# PR9022.net
KiCad netlist of a schematic drawn in EAGLE
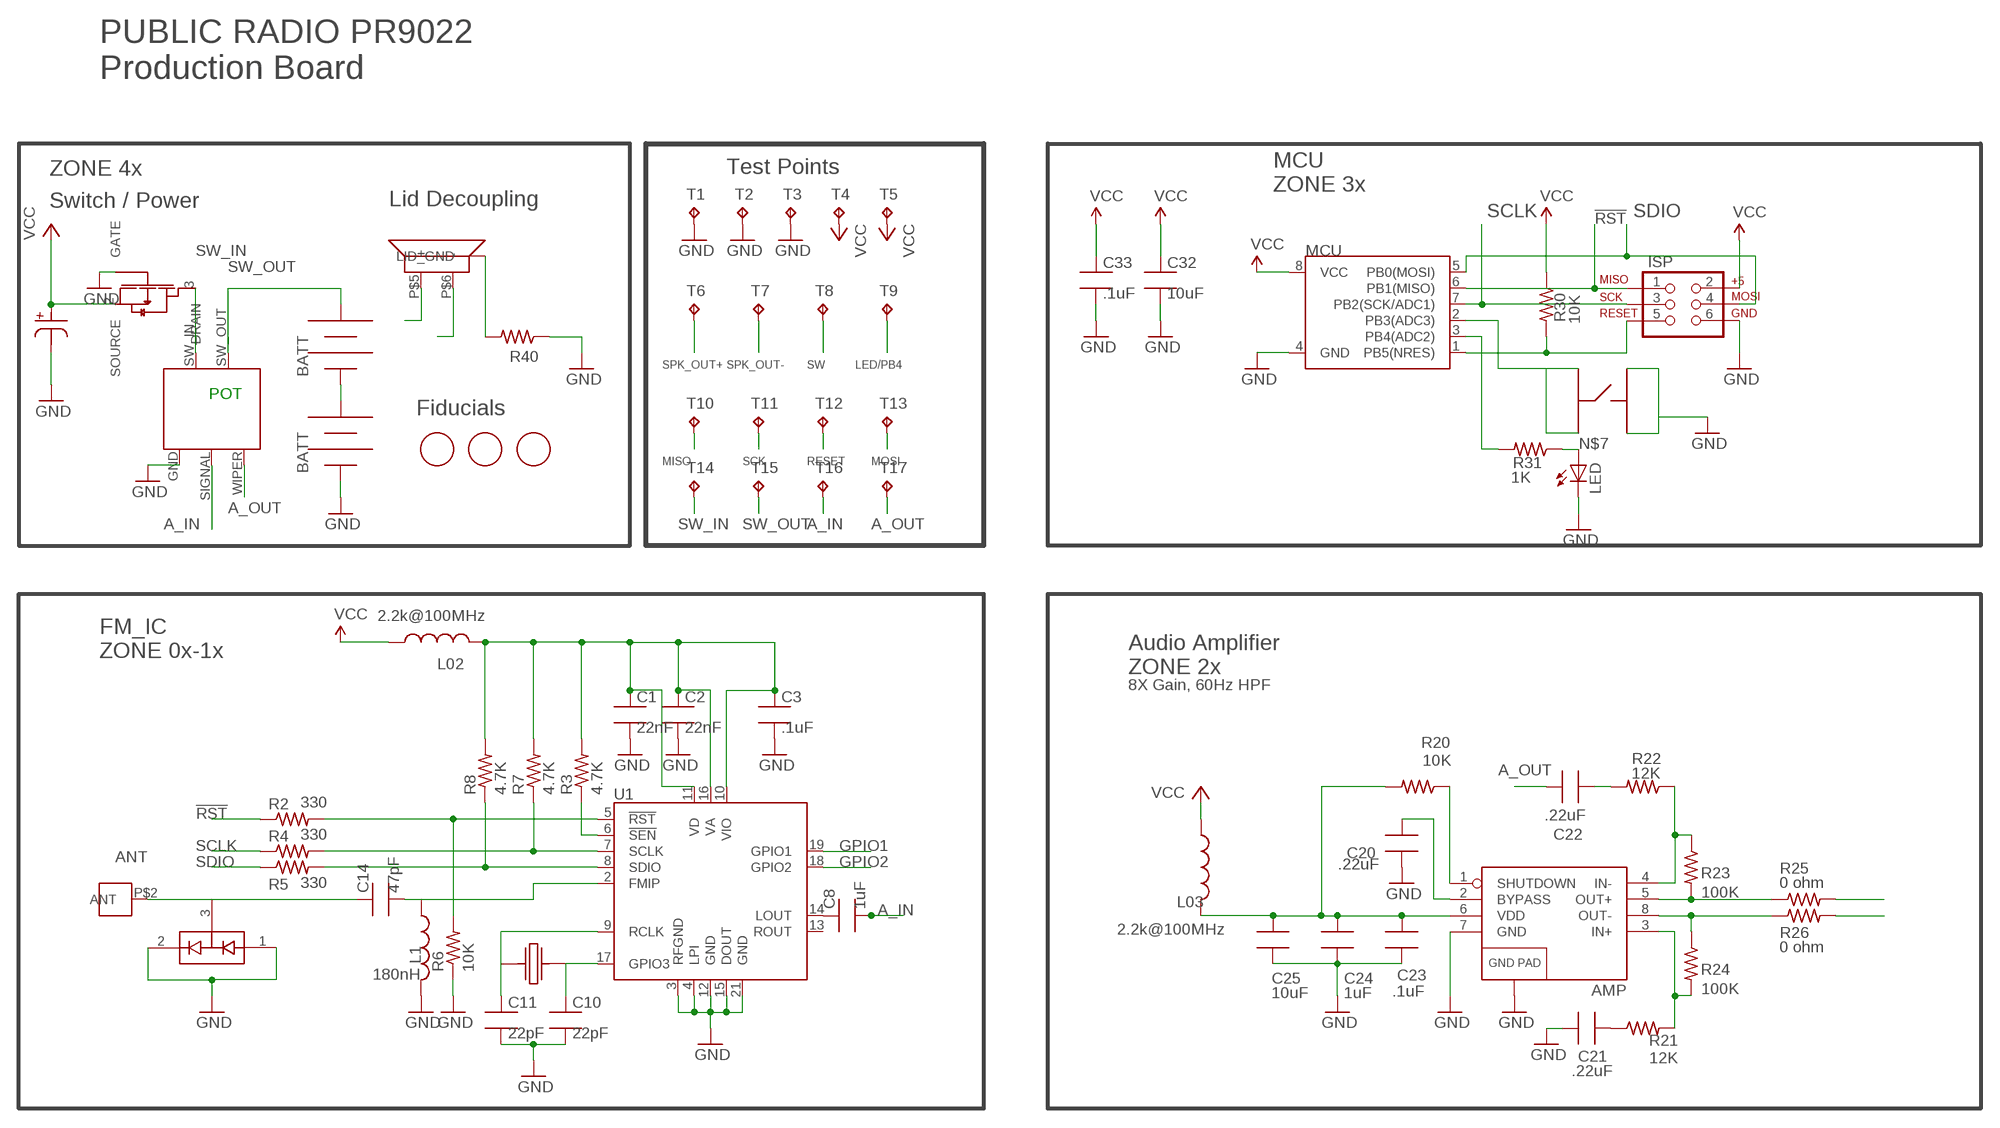
[diagram p0: schematic, sheet 1]

(export (version "E")
  (design (tool "Eeschema 10.0.6"))
  (components
    (comp (ref "AMP")
      (value "TPA6203A1")
      (footprint "eagle-import:8-MSOP")
      (libsource (lib "eagle-import") (part "TPA6203A1"))
    )
    (comp (ref "ANT_MOUNT")
      (value "DNP")
      (footprint "eagle-import:PEM_M3")
      (libsource (lib "eagle-import") (part "M3_PEMNUT"))
    )
    (comp (ref "C1")
      (value "22nF")
      (footprint "eagle-import:0603_CPL")
      (fields
        (field (name "MFG_PN") "CL10B223KB8NNNC")
        (field (name "TOL") "10%")
        (field (name "VOLTAGE") "16V")
      )
      (libsource (lib "eagle-import") (part "C_SMT_0603_CPL"))
    )
    (comp (ref "C2")
      (value "22nF")
      (footprint "eagle-import:0603_CPL")
      (fields
        (field (name "MFG_PN") "CL10B223KB8NNNC")
        (field (name "TOL") "10%")
        (field (name "VOLTAGE") "16V")
      )
      (libsource (lib "eagle-import") (part "C_SMT_0603_CPL"))
    )
    (comp (ref "C3")
      (value ".1uF")
      (footprint "eagle-import:0603_CPL")
      (fields
        (field (name "MFG_PN") "CL10B104KB8SFNC")
        (field (name "TOL") "10%")
        (field (name "VOLTAGE") "16V")
      )
      (libsource (lib "eagle-import") (part "C_SMT_0603_CPL"))
    )
    (comp (ref "C8")
      (value "1uF")
      (footprint "eagle-import:0603_CPL")
      (fields
        (field (name "MFG_PN") "CL10B105KP8NNNC")
        (field (name "TOL") "10%")
        (field (name "VOLTAGE") "10V")
      )
      (libsource (lib "eagle-import") (part "C_SMT_0603_CPL"))
    )
    (comp (ref "C10")
      (value "22pF")
      (footprint "eagle-import:0603_CPL")
      (fields
        (field (name "MFG_PN") "C1608C0G1H220J080AA")
        (field (name "TOL") "5%")
        (field (name "VOLTAGE") "50V")
      )
      (libsource (lib "eagle-import") (part "C_SMT_0603_CPL"))
    )
    (comp (ref "C11")
      (value "22pF")
      (footprint "eagle-import:0603_CPL")
      (fields
        (field (name "MFG_PN") "C1608C0G1H220J080AA")
        (field (name "TOL") "5%")
        (field (name "VOLTAGE") "50V")
      )
      (libsource (lib "eagle-import") (part "C_SMT_0603_CPL"))
    )
    (comp (ref "C14")
      (value "47pF")
      (footprint "eagle-import:0603_CPL")
      (fields
        (field (name "MFG_PN") "CL10C470JB8NCNC")
        (field (name "TOL") "5%")
        (field (name "VOLTAGE") "50V")
      )
      (libsource (lib "eagle-import") (part "C_SMT_0603_CPL"))
    )
    (comp (ref "C20")
      (value ".22uF")
      (footprint "eagle-import:0603_CPL")
      (fields
        (field (name "MFG_PN") "C1608X7R1C224K080AC")
        (field (name "TOL") "10%")
        (field (name "VOLTAGE") "16V")
      )
      (libsource (lib "eagle-import") (part "C_SMT_0603_CPL"))
    )
    (comp (ref "C21")
      (value ".22uF")
      (footprint "eagle-import:0603_CPL")
      (fields
        (field (name "MFG_PN") "C1608X7R1C224K080AC")
        (field (name "TOL") "10%")
        (field (name "VOLTAGE") "16V")
      )
      (libsource (lib "eagle-import") (part "C_SMT_0603_CPL"))
    )
    (comp (ref "C22")
      (value ".22uF")
      (footprint "eagle-import:0603_CPL")
      (fields
        (field (name "MFG_PN") "C1608X7R1C224K080AC")
        (field (name "TOL") "10%")
        (field (name "VOLTAGE") "16V")
      )
      (libsource (lib "eagle-import") (part "C_SMT_0603_CPL"))
    )
    (comp (ref "C23")
      (value ".1uF")
      (footprint "eagle-import:0603_CPL")
      (fields
        (field (name "MFG_PN") "CL10B104KB8SFNC")
        (field (name "TOL") "10%")
        (field (name "VOLTAGE") "16V")
      )
      (libsource (lib "eagle-import") (part "C_SMT_0603_CPL"))
    )
    (comp (ref "C24")
      (value "1uF")
      (footprint "eagle-import:0603_CPL")
      (fields
        (field (name "MFG_PN") "CL10B105KP8NNNC")
        (field (name "TOL") "10%")
        (field (name "VOLTAGE") "10V")
      )
      (libsource (lib "eagle-import") (part "C_SMT_0603_CPL"))
    )
    (comp (ref "C25")
      (value "10uF")
      (footprint "eagle-import:0603_CPL")
      (fields
        (field (name "MFG_PN") "CL10A106MQ8NNNC")
        (field (name "TOL") "20%")
        (field (name "VOLTAGE") "6.3V")
      )
      (libsource (lib "eagle-import") (part "C_SMT_0603_CPL"))
    )
    (comp (ref "C32")
      (value "10uF")
      (footprint "eagle-import:0603_CPL")
      (fields
        (field (name "MFG_PN") "CL10A106MQ8NNNC")
        (field (name "TOL") "20%")
        (field (name "VOLTAGE") "6.3V")
      )
      (libsource (lib "eagle-import") (part "C_SMT_0603_CPL"))
    )
    (comp (ref "C33")
      (value ".1uF")
      (footprint "eagle-import:0603_CPL")
      (fields
        (field (name "MFG_PN") "CL10B104KB8SFNC")
        (field (name "TOL") "10%")
        (field (name "VOLTAGE") "16V")
      )
      (libsource (lib "eagle-import") (part "C_SMT_0603_CPL"))
    )
    (comp (ref "C40")
      (value "220uF")
      (footprint "eagle-import:NICHICON_UD_63")
      (fields (field (name "TOL") "20%") (field (name "VOLTAGE") "16V"))
      (libsource (lib "eagle-import") (part "NICHICON_SERIESUD"))
    )
    (comp (ref "D1")
      (value "BAV99")
      (footprint "eagle-import:SOT23_CPL")
      (fields (field (name "MFG_PN") "BAV99,215"))
      (libsource (lib "eagle-import") (part "BAV99"))
    )
    (comp (ref "FET1")
      (value "AO3435")
      (footprint "eagle-import:SOT23_CPL")
      (fields (field (name "MFG_PN") "AO3435"))
      (libsource (lib "eagle-import") (part "AO3435"))
    )
    (comp (ref "ISP")
      (value "AVR_SPI_PRG_6NS")
      (footprint "eagle-import:2X3-NS")
      (libsource (lib "eagle-import") (part "AVR_SPI_PRG_6NS"))
    )
    (comp (ref "JP5")
      (value "BK-92_MPD_AA_BATT_CLIP")
      (footprint "eagle-import:BK92_AA_BATT")
      (fields (field (name "MFG_PN") "2 of BK92 - supplied by CL Labs"))
      (libsource (lib "eagle-import") (part "BK-92_MPD_AA_BATT_CLIP"))
    )
    (comp (ref "JP6")
      (value "BK-92_MPD_AA_BATT_CLIP")
      (footprint "eagle-import:BK92_AA_BATT")
      (fields (field (name "MFG_PN") "2 of BK92 - supplied by CL Labs"))
      (libsource (lib "eagle-import") (part "BK-92_MPD_AA_BATT_CLIP"))
    )
    (comp (ref "L1")
      (value "180nH")
      (footprint "eagle-import:0805_ADAFRUIT")
      (fields
        (field (name "CURRENT") "400mA")
        (field (name "DCR") "640m")
        (field (name "MFG_PN") "AISC-0805-R18J-T")
        (field (name "TOL") "5%")
      )
      (libsource (lib "eagle-import") (part "L_SMT_0805_ADAFRUIT"))
    )
    (comp (ref "L02")
      (value "2.2k@100MHz")
      (footprint "eagle-import:0603_CPL")
      (fields
        (field (name "CURRENT") "150mA")
        (field (name "DCR") "2.3")
        (field (name "MFG_PN") "HZ0603A222R-10")
      )
      (libsource (lib "eagle-import") (part "L_SMT_0603_CPL"))
    )
    (comp (ref "L03")
      (value "2.2k@100MHz")
      (footprint "eagle-import:0603_CPL")
      (fields
        (field (name "CURRENT") "150mA")
        (field (name "DCR") "2.3")
        (field (name "MFG_PN") "HZ0603A222R-10")
      )
      (libsource (lib "eagle-import") (part "L_SMT_0603_CPL"))
    )
    (comp (ref "LED")
      (value "LEDCHIPLED_0805")
      (footprint "eagle-import:CHIPLED_0805")
      (libsource (lib "eagle-import") (part "LEDCHIPLED_0805"))
    )
    (comp (ref "MARK1")
      (value "FIDUCIAL")
      (footprint "eagle-import:FIDUCIAL_1MM")
      (libsource (lib "eagle-import") (part "FIDUCIAL"))
    )
    (comp (ref "MARK2")
      (value "FIDUCIAL")
      (footprint "eagle-import:FIDUCIAL_1MM")
      (libsource (lib "eagle-import") (part "FIDUCIAL"))
    )
    (comp (ref "MARK3")
      (value "FIDUCIAL")
      (footprint "eagle-import:FIDUCIAL_1MM")
      (libsource (lib "eagle-import") (part "FIDUCIAL"))
    )
    (comp (ref "MCU")
      (value "ATTINY45TINY45-20-SMT")
      (footprint "eagle-import:8-SOIC")
      (libsource (lib "eagle-import") (part "ATTINY45TINY45-20-SMT"))
    )
    (comp (ref "R1")
      (value "RV170SF_TAIWANA_POT_SW")
      (footprint "eagle-import:RV170SF_SW_POT")
      (fields (field (name "MFG_PN") "RV170SF-43-20F-A10K - supplied by CL Labs"))
      (libsource (lib "eagle-import") (part "RV170SF_TAIWANA_POT_SW"))
    )
    (comp (ref "R2")
      (value "330")
      (footprint "eagle-import:0603_CPL")
      (fields (field (name "MFG_PN") "MCR03ERTJ331") (field (name "POWER") "1/10W") (field (name "TOL") "5%"))
      (libsource (lib "eagle-import") (part "R_SMT_R0603_CPL"))
    )
    (comp (ref "R3")
      (value "4.7K")
      (footprint "eagle-import:0603_CPL")
      (fields
        (field (name "MFG_PN") "ERJ-3EKF4701V")
        (field (name "POWER") "1/10W")
        (field (name "TOL") "1%")
      )
      (libsource (lib "eagle-import") (part "R_SMT_R0603_CPL"))
    )
    (comp (ref "R4")
      (value "330")
      (footprint "eagle-import:0603_CPL")
      (fields (field (name "MFG_PN") "MCR03ERTJ331") (field (name "POWER") "1/10W") (field (name "TOL") "5%"))
      (libsource (lib "eagle-import") (part "R_SMT_R0603_CPL"))
    )
    (comp (ref "R5")
      (value "330")
      (footprint "eagle-import:0603_CPL")
      (fields (field (name "MFG_PN") "MCR03ERTJ331") (field (name "POWER") "1/10W") (field (name "TOL") "5%"))
      (libsource (lib "eagle-import") (part "R_SMT_R0603_CPL"))
    )
    (comp (ref "R6")
      (value "10K")
      (footprint "eagle-import:0603_CPL")
      (fields
        (field (name "MFG_PN") "ERJ-3GEYJ103V")
        (field (name "POWER") "1/10W")
        (field (name "TOL") "5%")
      )
      (libsource (lib "eagle-import") (part "R_SMT_R0603_CPL"))
    )
    (comp (ref "R7")
      (value "4.7K")
      (footprint "eagle-import:0603_CPL")
      (fields
        (field (name "MFG_PN") "ERJ-3EKF4701V")
        (field (name "POWER") "1/10W")
        (field (name "TOL") "1%")
      )
      (libsource (lib "eagle-import") (part "R_SMT_R0603_CPL"))
    )
    (comp (ref "R8")
      (value "4.7K")
      (footprint "eagle-import:0603_CPL")
      (fields
        (field (name "MFG_PN") "ERJ-3EKF4701V")
        (field (name "POWER") "1/10W")
        (field (name "TOL") "1%")
      )
      (libsource (lib "eagle-import") (part "R_SMT_R0603_CPL"))
    )
    (comp (ref "R20")
      (value "10K")
      (footprint "eagle-import:0603_CPL")
      (fields
        (field (name "MFG_PN") "ERJ-3GEYJ103V")
        (field (name "POWER") "1/10W")
        (field (name "TOL") "5%")
      )
      (libsource (lib "eagle-import") (part "R_SMT_R0603_CPL"))
    )
    (comp (ref "R21")
      (value "12K")
      (footprint "eagle-import:0603_CPL")
      (fields
        (field (name "MFG_PN") "RC0603FR-0712KL")
        (field (name "POWER") "1/10W")
        (field (name "TOL") "1%")
      )
      (libsource (lib "eagle-import") (part "R_SMT_R0603_CPL"))
    )
    (comp (ref "R22")
      (value "12K")
      (footprint "eagle-import:0603_CPL")
      (fields
        (field (name "MFG_PN") "RC0603FR-0712KL")
        (field (name "POWER") "1/10W")
        (field (name "TOL") "1%")
      )
      (libsource (lib "eagle-import") (part "R_SMT_R0603_CPL"))
    )
    (comp (ref "R23")
      (value "100K")
      (footprint "eagle-import:0603_CPL")
      (fields
        (field (name "MFG_PN") "ERJ-3EKF1003V")
        (field (name "POWER") "1/10W")
        (field (name "TOL") "1%")
      )
      (libsource (lib "eagle-import") (part "R_SMT_R0603_CPL"))
    )
    (comp (ref "R24")
      (value "100K")
      (footprint "eagle-import:0603_CPL")
      (fields
        (field (name "MFG_PN") "ERJ-3EKF1003V")
        (field (name "POWER") "1/10W")
        (field (name "TOL") "1%")
      )
      (libsource (lib "eagle-import") (part "R_SMT_R0603_CPL"))
    )
    (comp (ref "R25")
      (value "0 ohm")
      (footprint "eagle-import:0805_ADAFRUIT")
      (fields (field (name "MFG_PN") "ERJ-6GEY0R00V "))
      (libsource (lib "eagle-import") (part "R_SMT_0805_ADAFRUIT"))
    )
    (comp (ref "R26")
      (value "0 ohm")
      (footprint "eagle-import:0805_ADAFRUIT")
      (fields (field (name "MFG_PN") "ERJ-6GEY0R00V "))
      (libsource (lib "eagle-import") (part "R_SMT_0805_ADAFRUIT"))
    )
    (comp (ref "R30")
      (value "10K")
      (footprint "eagle-import:0603_CPL")
      (fields
        (field (name "MFG_PN") "ERJ-3GEYJ103V")
        (field (name "POWER") "1/10W")
        (field (name "TOL") "5%")
      )
      (libsource (lib "eagle-import") (part "R_SMT_R0603_CPL"))
    )
    (comp (ref "R31")
      (value "1K")
      (footprint "eagle-import:0603_CPL")
      (fields
        (field (name "MFG_PN") "ERJ-3EKF1001V")
        (field (name "POWER") "1/10W")
        (field (name "TOL") "1%")
      )
      (libsource (lib "eagle-import") (part "R_SMT_R0603_CPL"))
    )
    (comp (ref "R40")
      (value "DNP")
      (footprint "eagle-import:0603_CPL")
      (fields (field (name "MFG_PN") "ERJ-3GEY0R00V"))
      (libsource (lib "eagle-import") (part "R_SMT_R0603_CPL"))
    )
    (comp (ref "SPKR_PLACE")
      (value "DNP")
      (footprint "eagle-import:PR2024_SPKR_PLACE")
      (libsource (lib "eagle-import") (part "PR9024_SPKR"))
    )
    (comp (ref "SW1")
      (value "C&K_PTS645")
      (footprint "eagle-import:C&K_PTS645_SMT")
      (libsource (lib "eagle-import") (part "C&K_PTS645"))
    )
    (comp (ref "T1")
      (value "TPTP20R")
      (footprint "eagle-import:TP20R")
      (libsource (lib "eagle-import") (part "TPTP20R"))
    )
    (comp (ref "T2")
      (value "TPTP20R")
      (footprint "eagle-import:TP20R")
      (libsource (lib "eagle-import") (part "TPTP20R"))
    )
    (comp (ref "T3")
      (value "TPTP20R")
      (footprint "eagle-import:TP20R")
      (libsource (lib "eagle-import") (part "TPTP20R"))
    )
    (comp (ref "T4")
      (value "TPTP20R")
      (footprint "eagle-import:TP20R")
      (libsource (lib "eagle-import") (part "TPTP20R"))
    )
    (comp (ref "T5")
      (value "TPTP20R")
      (footprint "eagle-import:TP20R")
      (libsource (lib "eagle-import") (part "TPTP20R"))
    )
    (comp (ref "T6")
      (value "TPTP20R")
      (footprint "eagle-import:TP20R")
      (libsource (lib "eagle-import") (part "TPTP20R"))
    )
    (comp (ref "T7")
      (value "TPTP20R")
      (footprint "eagle-import:TP20R")
      (libsource (lib "eagle-import") (part "TPTP20R"))
    )
    (comp (ref "T8")
      (value "TPTP20R")
      (footprint "eagle-import:TP20R")
      (libsource (lib "eagle-import") (part "TPTP20R"))
    )
    (comp (ref "T9")
      (value "TPTP20R")
      (footprint "eagle-import:TP20R")
      (libsource (lib "eagle-import") (part "TPTP20R"))
    )
    (comp (ref "T10")
      (value "TPTP20R")
      (footprint "eagle-import:TP20R")
      (libsource (lib "eagle-import") (part "TPTP20R"))
    )
    (comp (ref "T11")
      (value "TPTP20R")
      (footprint "eagle-import:TP20R")
      (libsource (lib "eagle-import") (part "TPTP20R"))
    )
    (comp (ref "T12")
      (value "TPTP20R")
      (footprint "eagle-import:TP20R")
      (libsource (lib "eagle-import") (part "TPTP20R"))
    )
    (comp (ref "T13")
      (value "TPTP20R")
      (footprint "eagle-import:TP20R")
      (libsource (lib "eagle-import") (part "TPTP20R"))
    )
    (comp (ref "T14")
      (value "TPTP20R")
      (footprint "eagle-import:TP20R")
      (libsource (lib "eagle-import") (part "TPTP20R"))
    )
    (comp (ref "T15")
      (value "TPTP20R")
      (footprint "eagle-import:TP20R")
      (libsource (lib "eagle-import") (part "TPTP20R"))
    )
    (comp (ref "T16")
      (value "TPTP20R")
      (footprint "eagle-import:TP20R")
      (libsource (lib "eagle-import") (part "TPTP20R"))
    )
    (comp (ref "T17")
      (value "TPTP20R")
      (footprint "eagle-import:TP20R")
      (libsource (lib "eagle-import") (part "TPTP20R"))
    )
    (comp (ref "U1")
      (value "SI4702-C19-GMR")
      (footprint "eagle-import:SI470X_20_QFN")
      (fields (field (name "MFG_PN") "Si4702 C19 GM - supplied by CL Labs"))
      (libsource (lib "eagle-import") (part "SI4702-C19-GMR"))
    )
    (comp (ref "X1")
      (value "ABS25XTAL")
      (footprint "eagle-import:4-SOJ")
      (libsource (lib "eagle-import") (part "ABS25XTAL"))
    )
  )
  (nets
    (net (code "1") (name "/ANT") (class "Default")
      (node (ref "ANT_MOUNT") (pin "P$2") (pinfunction "ANT_P$2") (pintype "bidirectional"))
      (node (ref "C14") (pin "1") (pinfunction "1_1") (pintype "passive"))
      (node (ref "D1") (pin "3") (pinfunction "COM_3") (pintype "bidirectional"))
    )
    (net (code "2") (name "/A_IN") (class "Default")
      (node (ref "C8") (pin "2") (pinfunction "2_2") (pintype "passive"))
      (node (ref "R1") (pin "SIGNAL") (pinfunction "SIGNAL_SIGNAL") (pintype "bidirectional"))
      (node (ref "T16") (pin "TP") (pinfunction "TP_TP") (pintype "input"))
    )
    (net (code "3") (name "/A_OUT") (class "Default")
      (node (ref "C22") (pin "2") (pinfunction "2_2") (pintype "passive"))
      (node (ref "R1") (pin "WIPER") (pinfunction "WIPER_WIPER") (pintype "bidirectional"))
      (node (ref "T17") (pin "TP") (pinfunction "TP_TP") (pintype "input"))
    )
    (net (code "4") (name "/GPIO1") (class "Default")
      (node (ref "U1") (pin "19") (pinfunction "GPIO1_19") (pintype "bidirectional"))
    )
    (net (code "5") (name "/GPIO2") (class "Default")
      (node (ref "U1") (pin "18") (pinfunction "GPIO2_18") (pintype "bidirectional"))
    )
    (net (code "6") (name "/LED{slash}PB4") (class "Default")
      (node (ref "MCU") (pin "3") (pinfunction "PB4(ADC2)_3") (pintype "bidirectional"))
      (node (ref "R31") (pin "2") (pinfunction "2_2") (pintype "passive"))
      (node (ref "T9") (pin "TP") (pinfunction "TP_TP") (pintype "input"))
    )
    (net (code "7") (name "/N$7") (class "Default")
      (node (ref "LED") (pin "A") (pinfunction "A_A") (pintype "passive"))
      (node (ref "R31") (pin "1") (pinfunction "1_1") (pintype "passive"))
    )
    (net (code "8") (name "/RESET") (class "Default")
      (node (ref "ISP") (pin "5") (pinfunction "5_5") (pintype "passive"))
      (node (ref "MCU") (pin "1") (pinfunction "PB5(NRES)_1") (pintype "bidirectional"))
      (node (ref "R30") (pin "2") (pinfunction "2_2") (pintype "passive"))
      (node (ref "T12") (pin "TP") (pinfunction "TP_TP") (pintype "input"))
    )
    (net (code "9") (name "/SCLK") (class "Default")
      (node (ref "ISP") (pin "3") (pinfunction "3_3") (pintype "passive"))
      (node (ref "MCU") (pin "7") (pinfunction "PB2(SCK/ADC1)_7") (pintype "bidirectional"))
      (node (ref "R4") (pin "1") (pinfunction "1_1") (pintype "passive"))
      (node (ref "T11") (pin "TP") (pinfunction "TP_TP") (pintype "input"))
    )
    (net (code "10") (name "/SDIO") (class "Default")
      (node (ref "ISP") (pin "4") (pinfunction "4_4") (pintype "passive"))
      (node (ref "MCU") (pin "5") (pinfunction "PB0(MOSI)_5") (pintype "bidirectional"))
      (node (ref "R5") (pin "1") (pinfunction "1_1") (pintype "passive"))
      (node (ref "T13") (pin "TP") (pinfunction "TP_TP") (pintype "input"))
    )
    (net (code "11") (name "/SPK_OUT+") (class "Default")
      (node (ref "R25") (pin "2") (pinfunction "2_2") (pintype "passive"))
      (node (ref "SPKR_PLACE") (pin "P$6") (pinfunction "-_P$6") (pintype "bidirectional"))
      (node (ref "T6") (pin "TP") (pinfunction "TP_TP") (pintype "input"))
    )
    (net (code "12") (name "/SPK_OUT-") (class "Default")
      (node (ref "R26") (pin "2") (pinfunction "2_2") (pintype "passive"))
      (node (ref "SPKR_PLACE") (pin "P$5") (pinfunction "+_P$5") (pintype "bidirectional"))
      (node (ref "T7") (pin "TP") (pinfunction "TP_TP") (pintype "input"))
    )
    (net (code "13") (name "/SW") (class "Default")
      (node (ref "MCU") (pin "2") (pinfunction "PB3(ADC3)_2") (pintype "bidirectional"))
      (node (ref "SW1") (pin "P$3") (pinfunction "P$3_P$3") (pintype "bidirectional"))
      (node (ref "SW1") (pin "P$4") (pinfunction "P$4_P$4") (pintype "bidirectional"))
      (node (ref "T8") (pin "TP") (pinfunction "TP_TP") (pintype "input"))
    )
    (net (code "14") (name "/SW_IN") (class "Default")
      (node (ref "FET1") (pin "3") (pinfunction "DRAIN_3") (pintype "bidirectional"))
      (node (ref "R1") (pin "SW_IN") (pinfunction "SW_IN_SW_IN") (pintype "bidirectional"))
      (node (ref "T14") (pin "TP") (pinfunction "TP_TP") (pintype "input"))
    )
    (net (code "15") (name "/SW_OUT") (class "Default")
      (node (ref "JP5") (pin "POS") (pinfunction "POS_POS") (pintype "bidirectional"))
      (node (ref "JP5") (pin "POS@2") (pinfunction "POS_POS@2") (pintype "bidirectional"))
      (node (ref "R1") (pin "SW_OUT") (pinfunction "SW_OUT_SW_OUT") (pintype "bidirectional"))
      (node (ref "T15") (pin "TP") (pinfunction "TP_TP") (pintype "input"))
    )
    (net (code "16") (name "/~{RST}") (class "Default")
      (node (ref "ISP") (pin "1") (pinfunction "1_1") (pintype "passive"))
      (node (ref "MCU") (pin "6") (pinfunction "PB1(MISO)_6") (pintype "bidirectional"))
      (node (ref "R2") (pin "1") (pinfunction "1_1") (pintype "passive"))
      (node (ref "T10") (pin "TP") (pinfunction "TP_TP") (pintype "input"))
    )
    (net (code "17") (name "GND") (class "Default")
      (node (ref "AMP") (pin "7") (pinfunction "GND_7") (pintype "power_in"))
      (node (ref "AMP") (pin "9") (pinfunction "GND_9") (pintype "power_in"))
      (node (ref "C1") (pin "2") (pinfunction "2_2") (pintype "passive"))
      (node (ref "C10") (pin "2") (pinfunction "2_2") (pintype "passive"))
      (node (ref "C11") (pin "2") (pinfunction "2_2") (pintype "passive"))
      (node (ref "C2") (pin "2") (pinfunction "2_2") (pintype "passive"))
      (node (ref "C20") (pin "1") (pinfunction "1_1") (pintype "passive"))
      (node (ref "C21") (pin "1") (pinfunction "1_1") (pintype "passive"))
      (node (ref "C23") (pin "2") (pinfunction "2_2") (pintype "passive"))
      (node (ref "C24") (pin "2") (pinfunction "2_2") (pintype "passive"))
      (node (ref "C25") (pin "2") (pinfunction "2_2") (pintype "passive"))
      (node (ref "C3") (pin "2") (pinfunction "2_2") (pintype "passive"))
      (node (ref "C32") (pin "2") (pinfunction "2_2") (pintype "passive"))
      (node (ref "C33") (pin "2") (pinfunction "2_2") (pintype "passive"))
      (node (ref "C40") (pin "P$2") (pinfunction "P$2_P$2") (pintype "bidirectional"))
      (node (ref "D1") (pin "1") (pinfunction "A1_1") (pintype "bidirectional"))
      (node (ref "D1") (pin "2") (pinfunction "C2_2") (pintype "bidirectional"))
      (node (ref "FET1") (pin "1") (pinfunction "GATE_1") (pintype "bidirectional"))
      (node (ref "ISP") (pin "6") (pinfunction "6_6") (pintype "passive"))
      (node (ref "JP6") (pin "NEG") (pinfunction "NEG_NEG") (pintype "bidirectional"))
      (node (ref "JP6") (pin "NEG@2") (pinfunction "NEG_NEG@2") (pintype "bidirectional"))
      (node (ref "L1") (pin "2") (pinfunction "2_2") (pintype "passive"))
      (node (ref "LED") (pin "C") (pinfunction "C_C") (pintype "passive"))
      (node (ref "MCU") (pin "4") (pinfunction "GND_4") (pintype "bidirectional"))
      (node (ref "R1") (pin "GND") (pinfunction "GND_GND") (pintype "bidirectional"))
      (node (ref "R40") (pin "1") (pinfunction "1_1") (pintype "passive"))
      (node (ref "R6") (pin "1") (pinfunction "1_1") (pintype "passive"))
      (node (ref "SW1") (pin "P$1") (pinfunction "P$1_P$1") (pintype "bidirectional"))
      (node (ref "SW1") (pin "P$2") (pinfunction "P$2_P$2") (pintype "bidirectional"))
      (node (ref "T1") (pin "TP") (pinfunction "TP_TP") (pintype "input"))
      (node (ref "T2") (pin "TP") (pinfunction "TP_TP") (pintype "input"))
      (node (ref "T3") (pin "TP") (pinfunction "TP_TP") (pintype "input"))
      (node (ref "U1") (pin "12") (pinfunction "GND_12") (pintype "bidirectional"))
      (node (ref "U1") (pin "15") (pinfunction "DOUT_15") (pintype "bidirectional"))
      (node (ref "U1") (pin "21") (pinfunction "GND_21") (pintype "bidirectional"))
      (node (ref "U1") (pin "3") (pinfunction "RFGND_3") (pintype "bidirectional"))
      (node (ref "U1") (pin "4") (pinfunction "LPI_4") (pintype "bidirectional"))
    )
    (net (code "18") (name "Net-(AMP-BYPASS)") (class "Default")
      (node (ref "AMP") (pin "2") (pinfunction "BYPASS_2") (pintype "bidirectional"))
      (node (ref "C20") (pin "2") (pinfunction "2_2") (pintype "passive"))
    )
    (net (code "19") (name "Net-(AMP-IN+)") (class "Default")
      (node (ref "AMP") (pin "3") (pinfunction "IN+_3") (pintype "bidirectional"))
      (node (ref "R21") (pin "2") (pinfunction "2_2") (pintype "passive"))
      (node (ref "R24") (pin "2") (pinfunction "2_2") (pintype "passive"))
    )
    (net (code "20") (name "Net-(AMP-IN-)") (class "Default")
      (node (ref "AMP") (pin "4") (pinfunction "IN-_4") (pintype "bidirectional"))
      (node (ref "R22") (pin "1") (pinfunction "1_1") (pintype "passive"))
      (node (ref "R23") (pin "1") (pinfunction "1_1") (pintype "passive"))
    )
    (net (code "21") (name "Net-(AMP-OUT+)") (class "Default")
      (node (ref "AMP") (pin "5") (pinfunction "OUT+_5") (pintype "bidirectional"))
      (node (ref "R23") (pin "2") (pinfunction "2_2") (pintype "passive"))
      (node (ref "R25") (pin "1") (pinfunction "1_1") (pintype "passive"))
    )
    (net (code "22") (name "Net-(AMP-OUT-)") (class "Default")
      (node (ref "AMP") (pin "8") (pinfunction "OUT-_8") (pintype "bidirectional"))
      (node (ref "R24") (pin "1") (pinfunction "1_1") (pintype "passive"))
      (node (ref "R26") (pin "1") (pinfunction "1_1") (pintype "passive"))
    )
    (net (code "23") (name "Net-(AMP-SHUTDOWN)") (class "Default")
      (node (ref "AMP") (pin "1") (pinfunction "SHUTDOWN_1") (pintype "input"))
      (node (ref "R20") (pin "1") (pinfunction "1_1") (pintype "passive"))
    )
    (net (code "24") (name "Net-(AMP-VDD)") (class "Default")
      (node (ref "AMP") (pin "6") (pinfunction "VDD_6") (pintype "power_in"))
      (node (ref "C23") (pin "1") (pinfunction "1_1") (pintype "passive"))
      (node (ref "C24") (pin "1") (pinfunction "1_1") (pintype "passive"))
      (node (ref "C25") (pin "1") (pinfunction "1_1") (pintype "passive"))
      (node (ref "L03") (pin "2") (pinfunction "2_2") (pintype "passive"))
      (node (ref "R20") (pin "2") (pinfunction "2_2") (pintype "passive"))
    )
    (net (code "25") (name "Net-(C21-Pad2)") (class "Default")
      (node (ref "C21") (pin "2") (pinfunction "2_2") (pintype "passive"))
      (node (ref "R21") (pin "1") (pinfunction "1_1") (pintype "passive"))
    )
    (net (code "26") (name "Net-(C22-Pad1)") (class "Default")
      (node (ref "C22") (pin "1") (pinfunction "1_1") (pintype "passive"))
      (node (ref "R22") (pin "2") (pinfunction "2_2") (pintype "passive"))
    )
    (net (code "27") (name "Net-(JP5-NEG-PadNEG@2)") (class "Default")
      (node (ref "JP5") (pin "NEG") (pinfunction "NEG_NEG") (pintype "bidirectional"))
      (node (ref "JP5") (pin "NEG@2") (pinfunction "NEG_NEG@2") (pintype "bidirectional"))
      (node (ref "JP6") (pin "POS") (pinfunction "POS_POS") (pintype "bidirectional"))
      (node (ref "JP6") (pin "POS@2") (pinfunction "POS_POS@2") (pintype "bidirectional"))
    )
    (net (code "28") (name "Net-(SPKR_PLACE-LID_GND)") (class "Default")
      (node (ref "R40") (pin "2") (pinfunction "2_2") (pintype "passive"))
      (node (ref "SPKR_PLACE") (pin "P$4") (pinfunction "LID_GND_P$4") (pintype "bidirectional"))
    )
    (net (code "29") (name "Net-(U1-FMIP)") (class "Default")
      (node (ref "C14") (pin "2") (pinfunction "2_2") (pintype "passive"))
      (node (ref "L1") (pin "1") (pinfunction "1_1") (pintype "passive"))
      (node (ref "U1") (pin "2") (pinfunction "FMIP_2") (pintype "bidirectional"))
    )
    (net (code "30") (name "Net-(U1-GPIO3)") (class "Default")
      (node (ref "C10") (pin "1") (pinfunction "1_1") (pintype "passive"))
      (node (ref "U1") (pin "17") (pinfunction "GPIO3_17") (pintype "bidirectional"))
      (node (ref "X1") (pin "P$4") (pinfunction "P$4_P$4") (pintype "bidirectional"))
    )
    (net (code "31") (name "Net-(U1-LOUT)") (class "Default")
      (node (ref "C8") (pin "1") (pinfunction "1_1") (pintype "passive"))
      (node (ref "U1") (pin "14") (pinfunction "LOUT_14") (pintype "bidirectional"))
    )
    (net (code "32") (name "Net-(U1-RCLK)") (class "Default")
      (node (ref "C11") (pin "1") (pinfunction "1_1") (pintype "passive"))
      (node (ref "U1") (pin "9") (pinfunction "RCLK_9") (pintype "bidirectional"))
      (node (ref "X1") (pin "P$1") (pinfunction "P$1_P$1") (pintype "bidirectional"))
    )
    (net (code "33") (name "Net-(U1-SCLK)") (class "Default")
      (node (ref "R4") (pin "2") (pinfunction "2_2") (pintype "passive"))
      (node (ref "R7") (pin "1") (pinfunction "1_1") (pintype "passive"))
      (node (ref "U1") (pin "7") (pinfunction "SCLK_7") (pintype "bidirectional"))
    )
    (net (code "34") (name "Net-(U1-SDIO)") (class "Default")
      (node (ref "R5") (pin "2") (pinfunction "2_2") (pintype "passive"))
      (node (ref "R8") (pin "1") (pinfunction "1_1") (pintype "passive"))
      (node (ref "U1") (pin "8") (pinfunction "SDIO_8") (pintype "bidirectional"))
    )
    (net (code "35") (name "Net-(U1-VA)") (class "Default")
      (node (ref "C1") (pin "1") (pinfunction "1_1") (pintype "passive"))
      (node (ref "C2") (pin "1") (pinfunction "1_1") (pintype "passive"))
      (node (ref "C3") (pin "1") (pinfunction "1_1") (pintype "passive"))
      (node (ref "L02") (pin "2") (pinfunction "2_2") (pintype "passive"))
      (node (ref "R3") (pin "2") (pinfunction "2_2") (pintype "passive"))
      (node (ref "R7") (pin "2") (pinfunction "2_2") (pintype "passive"))
      (node (ref "R8") (pin "2") (pinfunction "2_2") (pintype "passive"))
      (node (ref "U1") (pin "10") (pinfunction "VIO_10") (pintype "bidirectional"))
      (node (ref "U1") (pin "11") (pinfunction "VD_11") (pintype "bidirectional"))
      (node (ref "U1") (pin "16") (pinfunction "VA_16") (pintype "bidirectional"))
    )
    (net (code "36") (name "Net-(U1-~{RST})") (class "Default")
      (node (ref "R2") (pin "2") (pinfunction "2_2") (pintype "passive"))
      (node (ref "R6") (pin "2") (pinfunction "2_2") (pintype "passive"))
      (node (ref "U1") (pin "5") (pinfunction "~{RST}_5") (pintype "bidirectional"))
    )
    (net (code "37") (name "Net-(U1-~{SEN})") (class "Default")
      (node (ref "R3") (pin "1") (pinfunction "1_1") (pintype "passive"))
      (node (ref "U1") (pin "6") (pinfunction "~{SEN}_6") (pintype "bidirectional"))
    )
    (net (code "38") (name "VCC") (class "Default")
      (node (ref "C32") (pin "1") (pinfunction "1_1") (pintype "passive"))
      (node (ref "C33") (pin "1") (pinfunction "1_1") (pintype "passive"))
      (node (ref "C40") (pin "P$1") (pinfunction "P$1_P$1") (pintype "bidirectional"))
      (node (ref "FET1") (pin "2") (pinfunction "SOURCE_2") (pintype "bidirectional"))
      (node (ref "ISP") (pin "2") (pinfunction "2_2") (pintype "passive"))
      (node (ref "L02") (pin "1") (pinfunction "1_1") (pintype "passive"))
      (node (ref "L03") (pin "1") (pinfunction "1_1") (pintype "passive"))
      (node (ref "MCU") (pin "8") (pinfunction "VCC_8") (pintype "bidirectional"))
      (node (ref "R30") (pin "1") (pinfunction "1_1") (pintype "passive"))
      (node (ref "T4") (pin "TP") (pinfunction "TP_TP") (pintype "input"))
      (node (ref "T5") (pin "TP") (pinfunction "TP_TP") (pintype "input"))
    )
    (net (code "39") (name "unconnected-(U1-ROUT-Pad13)") (class "Default")
      (node (ref "U1") (pin "13") (pinfunction "ROUT_13") (pintype "bidirectional"))
    )
  )
)
